# 555_Astable.net
KiCad netlist of a schematic drawn in Altium Designer
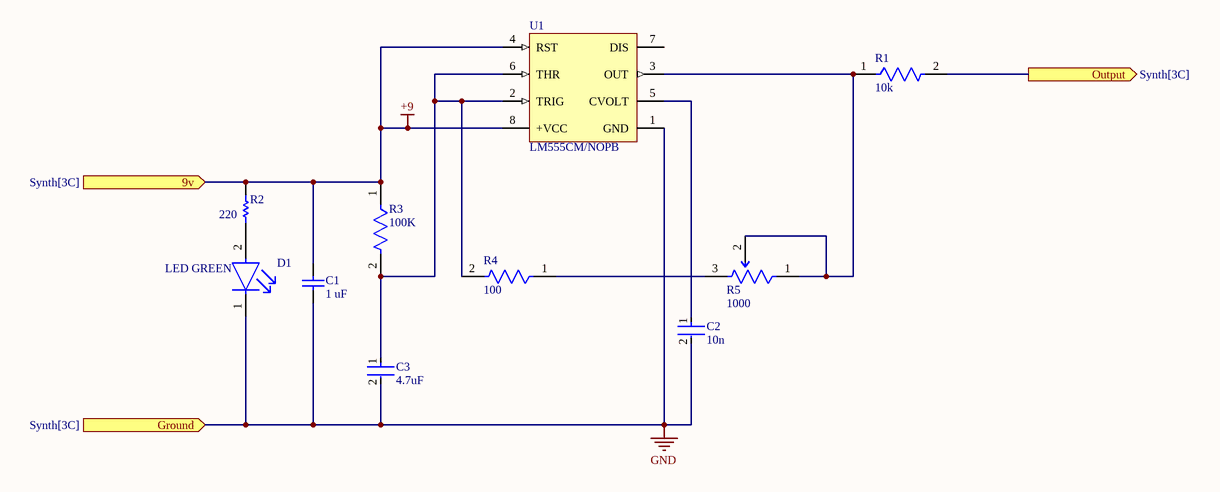
[diagram p0: 555_Astable.SchDoc]

(export (version "E")
  (design (tool "Eeschema 10.0.6"))
  (components
    (comp (ref "C1")
      (value "1 uF")
      (footprint "CAPC3216X110X50LL20T25")
      (description "Chip Capacitor, 1 uF, +/- 10%, 50 V, -55 to 125 degC, 1206 (3216 Metric), RoHS, Tape and Reel")
      (fields (field (name "MANUFACTURER") "Kemet") (field (name "TOLERANCE") "10%"))
      (libsource (lib "Altium Content Vault") (part "CAP-NP-2"))
    )
    (comp (ref "C2")
      (value "10n")
      (footprint "FP-C0805C-DN-MFG")
      (description "C0805 10,000 pF X7R 30ppm/°C 10.00% 200 V")
      (fields (field (name "OCTOPART") "https://octopart.com/c0805c103k2ractu-kemet-9138347"))
      (libsource (lib "Altium Content Vault") (part "b4654b650e69147ec39a6b967a45e02"))
    )
    (comp (ref "C3")
      (value "4.7uF")
      (footprint "FP-CL282-IPC_C")
      (description "Cap Ceramic 4.7uF 10V X5R ±20% SMD 0402 +85°C Paper T/R 4.7uF CL05A475MP5NRNC")
      (fields (field (name "TOLERANCE") "20%"))
      (libsource (lib "Altium Content Vault") (part "b4654b650e69147ec39a6b967a45e02"))
    )
    (comp (ref "D1")
      (value "LED GREEN")
      (footprint "FP-LTST-C190GKT-MFG")
      (description "LED GREEN CLEAR CHIP SMDLTST-C190GKT")
      (fields (field (name "VOLTAGE") "2V"))
      (libsource (lib "Altium Content Vault") (part "8706943c75ba83719d021d2fdc84c58"))
    )
    (comp (ref "R1")
      (value "10k")
      (footprint "FP-RT0603-MFG")
      (description "RES SMD 10K OHM 1% 1/10W 0603 RT0603FRE0710KL")
      (fields
        (field (name "MANUFACTURER") "Yageo")
        (field (name "OCTOPART") "https://octopart.com/rt0603fre0710kl-yageo-40009243")
      )
      (libsource (lib "Altium Content Vault") (part "1029c3af85768c4190bb7ad29bc67b5"))
    )
    (comp (ref "R2")
      (value "220")
      (footprint "RESC3216X60X45ML10T20")
      (description "CRCW1206220RFKEA")
      (fields (field (name "MANUFACTURER") "Vishay Dale"))
      (libsource (lib "Altium Content Vault") (part "RES"))
    )
    (comp (ref "R3")
      (value "100K")
      (footprint "FP-RC0603-0_55-MFG")
      (description "RES SMD 100K OHM 1% 1/10W 0603 RC0603FR-07100KL")
      (fields (field (name "TOLERANCE") "1%"))
      (libsource (lib "Altium Content Vault") (part "1029c3af85768c4190bb7ad29bc67b5"))
    )
    (comp (ref "R4")
      (value "100")
      (footprint "FP-ERJ1GN-MFG")
      (description "RES SMD 100 OHM 1% 1/20W 0201ERJ-1GNF1000C")
      (fields
        (field (name "MANUFACTURER") "Panasonic Electronic Components")
        (field (name "OCTOPART") "https://octopart.com/erj-1gnf1000c-panasonic-55419695")
      )
      (libsource (lib "Altium Content Vault") (part "1029c3af85768c4190bb7ad29bc67b5"))
    )
    (comp (ref "R5")
      (value "1000")
      (footprint "FP-3362P-1-102TLF-MFG")
      (description "TRIMMER 1K OHM 0.5W PC PIN TOP 3362P-1-102TLF")
      (fields (field (name "TOLERANCE") "10%"))
      (libsource (lib "Altium Content Vault") (part "2dcfd2547301a7d3209a5e99acfd772"))
    )
    (comp (ref "U1")
      (value "LM555CM/NOPB")
      (footprint "D0008A_M")
      (description "Timer, 8-pin Narrow SOIC, Pb-Free")
      (fields (field (name "MANUFACTURER") "Texas Instruments"))
      (libsource (lib "Altium Content Vault") (part "AN-TIMER-LM555-8"))
    )
  )
  (nets
    (net (code "1") (name "+9") (class "Default")
      (node (ref "C1") (pin "2") (pinfunction "2_2") (pintype "passive"))
      (node (ref "R2") (pin "1") (pinfunction "1_1") (pintype "passive"))
      (node (ref "R3") (pin "1") (pinfunction "1_1") (pintype "passive"))
      (node (ref "U1") (pin "4") (pinfunction "RST_4") (pintype "input"))
      (node (ref "U1") (pin "8") (pinfunction "+VCC_8") (pintype "power_in"))
    )
    (net (code "2") (name "/Output") (class "Default")
      (node (ref "R1") (pin "2") (pinfunction "2_2") (pintype "passive"))
    )
    (net (code "3") (name "GND") (class "Default")
      (node (ref "C1") (pin "1") (pinfunction "1_1") (pintype "passive"))
      (node (ref "C2") (pin "2") (pinfunction "2_2") (pintype "passive"))
      (node (ref "C3") (pin "2") (pinfunction "2_2") (pintype "passive"))
      (node (ref "D1") (pin "1") (pinfunction "C_1") (pintype "passive"))
      (node (ref "U1") (pin "1") (pinfunction "GND_1") (pintype "power_in"))
    )
    (net (code "4") (name "Net-(D1-A)") (class "Default")
      (node (ref "D1") (pin "2") (pinfunction "A_2") (pintype "passive"))
      (node (ref "R2") (pin "2") (pinfunction "2_2") (pintype "passive"))
    )
    (net (code "5") (name "Net-(R5-CCW)") (class "Default")
      (node (ref "R1") (pin "1") (pinfunction "1_1") (pintype "passive"))
      (node (ref "R5") (pin "1") (pinfunction "CCW_1") (pintype "passive"))
      (node (ref "R5") (pin "2") (pinfunction "WIPER_2") (pintype "passive"))
      (node (ref "U1") (pin "3") (pinfunction "OUT_3") (pintype "output"))
    )
    (net (code "6") (name "Net-(R5-CW)") (class "Default")
      (node (ref "R4") (pin "1") (pinfunction "1_1") (pintype "passive"))
      (node (ref "R5") (pin "3") (pinfunction "CW_3") (pintype "passive"))
    )
    (net (code "7") (name "Net-(U1-CVOLT)") (class "Default")
      (node (ref "C2") (pin "1") (pinfunction "1_1") (pintype "passive"))
      (node (ref "U1") (pin "5") (pinfunction "CVOLT_5") (pintype "passive"))
    )
    (net (code "8") (name "Net-(U1-THR)") (class "Default")
      (node (ref "C3") (pin "1") (pinfunction "1_1") (pintype "passive"))
      (node (ref "R3") (pin "2") (pinfunction "2_2") (pintype "passive"))
      (node (ref "R4") (pin "2") (pinfunction "2_2") (pintype "passive"))
      (node (ref "U1") (pin "2") (pinfunction "TRIG_2") (pintype "input"))
      (node (ref "U1") (pin "6") (pinfunction "THR_6") (pintype "input"))
    )
    (net (code "9") (name "unconnected-(U1-DIS-Pad7)") (class "Default")
      (node (ref "U1") (pin "7") (pinfunction "DIS_7") (pintype "open_collector"))
    )
  )
)
